# MBR.net
KiCad netlist of a schematic drawn in EAGLE
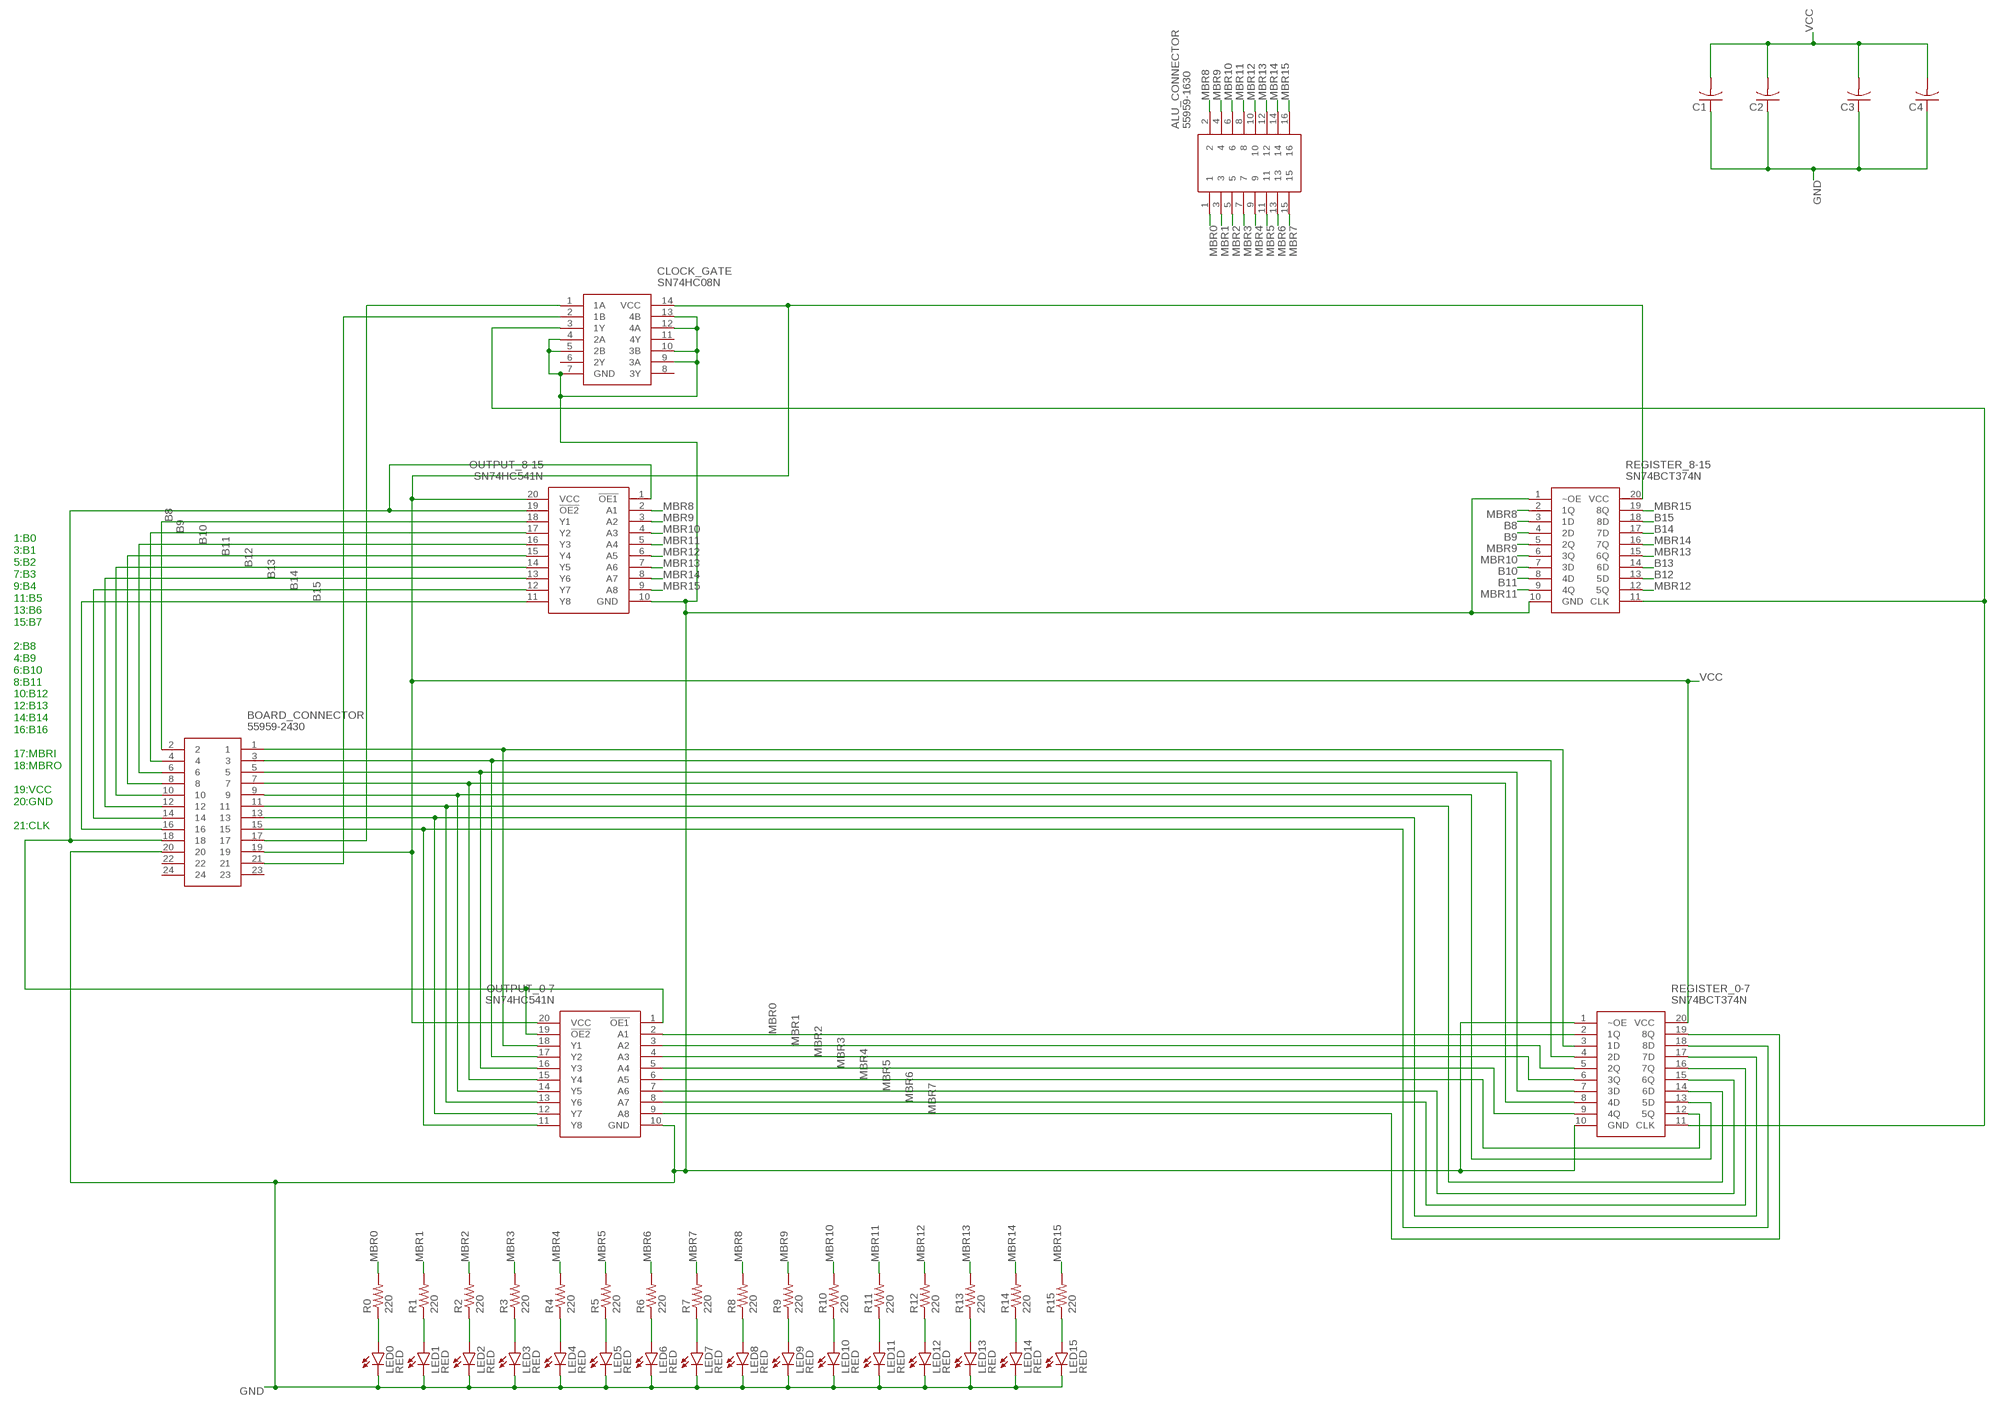
[diagram p0: schematic, sheet 1]

(export (version "E")
  (design (tool "Eeschema 10.0.6"))
  (components
    (comp (ref "ALU_CONNECTOR")
      (value "55959-1630")
      (footprint "eagle-import:SHDR16W65P250X200_2X8_1940X140")
      (fields (field (name "MOUSER_PART_NUMBER") "538-55959-1630"))
      (libsource (lib "eagle-import") (part "55959-1630"))
    )
    (comp (ref "BOARD_CONNECTOR")
      (value "55959-2430")
      (footprint "eagle-import:559592430")
      (fields (field (name "MOUSER_PART_NUMBER") "538-55959-2430"))
      (libsource (lib "eagle-import") (part "55959-2430"))
    )
    (comp (ref "C1")
      (value "C-US025-024X044")
      (footprint "eagle-import:C025-024X044")
      (libsource (lib "eagle-import") (part "C-US025-024X044"))
    )
    (comp (ref "C2")
      (value "C-US025-024X044")
      (footprint "eagle-import:C025-024X044")
      (libsource (lib "eagle-import") (part "C-US025-024X044"))
    )
    (comp (ref "C3")
      (value "C-US025-024X044")
      (footprint "eagle-import:C025-024X044")
      (libsource (lib "eagle-import") (part "C-US025-024X044"))
    )
    (comp (ref "C4")
      (value "C-US025-024X044")
      (footprint "eagle-import:C025-024X044")
      (libsource (lib "eagle-import") (part "C-US025-024X044"))
    )
    (comp (ref "CLOCK_GATE")
      (value "SN74HC08N")
      (footprint "eagle-import:DIP794W53P254L1930H508Q14N")
      (fields (field (name "MOUSER_PART_NUMBER") "595-SN74HC08N"))
      (libsource (lib "eagle-import") (part "SN74HC08N"))
    )
    (comp (ref "LED0")
      (value "RED")
      (footprint "eagle-import:LED3MM")
      (libsource (lib "eagle-import") (part "LED3MM"))
    )
    (comp (ref "LED1")
      (value "RED")
      (footprint "eagle-import:LED3MM")
      (libsource (lib "eagle-import") (part "LED3MM"))
    )
    (comp (ref "LED2")
      (value "RED")
      (footprint "eagle-import:LED3MM")
      (libsource (lib "eagle-import") (part "LED3MM"))
    )
    (comp (ref "LED3")
      (value "RED")
      (footprint "eagle-import:LED3MM")
      (libsource (lib "eagle-import") (part "LED3MM"))
    )
    (comp (ref "LED4")
      (value "RED")
      (footprint "eagle-import:LED3MM")
      (libsource (lib "eagle-import") (part "LED3MM"))
    )
    (comp (ref "LED5")
      (value "RED")
      (footprint "eagle-import:LED3MM")
      (libsource (lib "eagle-import") (part "LED3MM"))
    )
    (comp (ref "LED6")
      (value "RED")
      (footprint "eagle-import:LED3MM")
      (libsource (lib "eagle-import") (part "LED3MM"))
    )
    (comp (ref "LED7")
      (value "RED")
      (footprint "eagle-import:LED3MM")
      (libsource (lib "eagle-import") (part "LED3MM"))
    )
    (comp (ref "LED8")
      (value "RED")
      (footprint "eagle-import:LED3MM")
      (libsource (lib "eagle-import") (part "LED3MM"))
    )
    (comp (ref "LED9")
      (value "RED")
      (footprint "eagle-import:LED3MM")
      (libsource (lib "eagle-import") (part "LED3MM"))
    )
    (comp (ref "LED10")
      (value "RED")
      (footprint "eagle-import:LED3MM")
      (libsource (lib "eagle-import") (part "LED3MM"))
    )
    (comp (ref "LED11")
      (value "RED")
      (footprint "eagle-import:LED3MM")
      (libsource (lib "eagle-import") (part "LED3MM"))
    )
    (comp (ref "LED12")
      (value "RED")
      (footprint "eagle-import:LED3MM")
      (libsource (lib "eagle-import") (part "LED3MM"))
    )
    (comp (ref "LED13")
      (value "RED")
      (footprint "eagle-import:LED3MM")
      (libsource (lib "eagle-import") (part "LED3MM"))
    )
    (comp (ref "LED14")
      (value "RED")
      (footprint "eagle-import:LED3MM")
      (libsource (lib "eagle-import") (part "LED3MM"))
    )
    (comp (ref "LED15")
      (value "RED")
      (footprint "eagle-import:LED3MM")
      (libsource (lib "eagle-import") (part "LED3MM"))
    )
    (comp (ref "OUTPUT_0-7")
      (value "SN74HC541N")
      (footprint "eagle-import:DIP794W53P254L2540H508Q20N")
      (fields (field (name "MOUSER_PART_NUMBER") "595-SN74HC541N"))
      (libsource (lib "eagle-import") (part "SN74HC541N"))
    )
    (comp (ref "OUTPUT_8-15")
      (value "SN74HC541N")
      (footprint "eagle-import:DIP794W53P254L2540H508Q20N")
      (fields (field (name "MOUSER_PART_NUMBER") "595-SN74HC541N"))
      (libsource (lib "eagle-import") (part "SN74HC541N"))
    )
    (comp (ref "R0")
      (value "220")
      (footprint "eagle-import:0204_7")
      (libsource (lib "eagle-import") (part "R-US_0204/7"))
    )
    (comp (ref "R1")
      (value "220")
      (footprint "eagle-import:0204_7")
      (libsource (lib "eagle-import") (part "R-US_0204/7"))
    )
    (comp (ref "R2")
      (value "220")
      (footprint "eagle-import:0204_7")
      (libsource (lib "eagle-import") (part "R-US_0204/7"))
    )
    (comp (ref "R3")
      (value "220")
      (footprint "eagle-import:0204_7")
      (libsource (lib "eagle-import") (part "R-US_0204/7"))
    )
    (comp (ref "R4")
      (value "220")
      (footprint "eagle-import:0204_7")
      (libsource (lib "eagle-import") (part "R-US_0204/7"))
    )
    (comp (ref "R5")
      (value "220")
      (footprint "eagle-import:0204_7")
      (libsource (lib "eagle-import") (part "R-US_0204/7"))
    )
    (comp (ref "R6")
      (value "220")
      (footprint "eagle-import:0204_7")
      (libsource (lib "eagle-import") (part "R-US_0204/7"))
    )
    (comp (ref "R7")
      (value "220")
      (footprint "eagle-import:0204_7")
      (libsource (lib "eagle-import") (part "R-US_0204/7"))
    )
    (comp (ref "R8")
      (value "220")
      (footprint "eagle-import:0204_7")
      (libsource (lib "eagle-import") (part "R-US_0204/7"))
    )
    (comp (ref "R9")
      (value "220")
      (footprint "eagle-import:0204_7")
      (libsource (lib "eagle-import") (part "R-US_0204/7"))
    )
    (comp (ref "R10")
      (value "220")
      (footprint "eagle-import:0204_7")
      (libsource (lib "eagle-import") (part "R-US_0204/7"))
    )
    (comp (ref "R11")
      (value "220")
      (footprint "eagle-import:0204_7")
      (libsource (lib "eagle-import") (part "R-US_0204/7"))
    )
    (comp (ref "R12")
      (value "220")
      (footprint "eagle-import:0204_7")
      (libsource (lib "eagle-import") (part "R-US_0204/7"))
    )
    (comp (ref "R13")
      (value "220")
      (footprint "eagle-import:0204_7")
      (libsource (lib "eagle-import") (part "R-US_0204/7"))
    )
    (comp (ref "R14")
      (value "220")
      (footprint "eagle-import:0204_7")
      (libsource (lib "eagle-import") (part "R-US_0204/7"))
    )
    (comp (ref "R15")
      (value "220")
      (footprint "eagle-import:0204_7")
      (libsource (lib "eagle-import") (part "R-US_0204/7"))
    )
    (comp (ref "REGISTER_0-7")
      (value "SN74BCT374N")
      (footprint "eagle-import:DIP254P762X508-20")
      (fields (field (name "MOUSER_PART_NUMBER") "595-SN74BCT374N"))
      (libsource (lib "eagle-import") (part "SN74BCT374N"))
    )
    (comp (ref "REGISTER_8-15")
      (value "SN74BCT374N")
      (footprint "eagle-import:DIP254P762X508-20")
      (fields (field (name "MOUSER_PART_NUMBER") "595-SN74BCT374N"))
      (libsource (lib "eagle-import") (part "SN74BCT374N"))
    )
  )
  (nets
    (net (code "1") (name "/B8") (class "Default")
      (node (ref "BOARD_CONNECTOR") (pin "2") (pinfunction "2_2") (pintype "bidirectional"))
      (node (ref "OUTPUT_8-15") (pin "18") (pinfunction "Y1_18") (pintype "bidirectional"))
      (node (ref "REGISTER_8-15") (pin "3") (pinfunction "1D_3") (pintype "bidirectional"))
    )
    (net (code "2") (name "/B9") (class "Default")
      (node (ref "BOARD_CONNECTOR") (pin "4") (pinfunction "4_4") (pintype "bidirectional"))
      (node (ref "OUTPUT_8-15") (pin "17") (pinfunction "Y2_17") (pintype "bidirectional"))
      (node (ref "REGISTER_8-15") (pin "4") (pinfunction "2D_4") (pintype "bidirectional"))
    )
    (net (code "3") (name "/B10") (class "Default")
      (node (ref "BOARD_CONNECTOR") (pin "6") (pinfunction "6_6") (pintype "bidirectional"))
      (node (ref "OUTPUT_8-15") (pin "16") (pinfunction "Y3_16") (pintype "bidirectional"))
      (node (ref "REGISTER_8-15") (pin "7") (pinfunction "3D_7") (pintype "bidirectional"))
    )
    (net (code "4") (name "/B11") (class "Default")
      (node (ref "BOARD_CONNECTOR") (pin "8") (pinfunction "8_8") (pintype "bidirectional"))
      (node (ref "OUTPUT_8-15") (pin "15") (pinfunction "Y4_15") (pintype "bidirectional"))
      (node (ref "REGISTER_8-15") (pin "8") (pinfunction "4D_8") (pintype "bidirectional"))
    )
    (net (code "5") (name "/B12") (class "Default")
      (node (ref "BOARD_CONNECTOR") (pin "10") (pinfunction "10_10") (pintype "bidirectional"))
      (node (ref "OUTPUT_8-15") (pin "14") (pinfunction "Y5_14") (pintype "bidirectional"))
      (node (ref "REGISTER_8-15") (pin "13") (pinfunction "5D_13") (pintype "bidirectional"))
    )
    (net (code "6") (name "/B13") (class "Default")
      (node (ref "BOARD_CONNECTOR") (pin "12") (pinfunction "12_12") (pintype "bidirectional"))
      (node (ref "OUTPUT_8-15") (pin "13") (pinfunction "Y6_13") (pintype "bidirectional"))
      (node (ref "REGISTER_8-15") (pin "14") (pinfunction "6D_14") (pintype "bidirectional"))
    )
    (net (code "7") (name "/B14") (class "Default")
      (node (ref "BOARD_CONNECTOR") (pin "14") (pinfunction "14_14") (pintype "bidirectional"))
      (node (ref "OUTPUT_8-15") (pin "12") (pinfunction "Y7_12") (pintype "bidirectional"))
      (node (ref "REGISTER_8-15") (pin "17") (pinfunction "7D_17") (pintype "bidirectional"))
    )
    (net (code "8") (name "/B15") (class "Default")
      (node (ref "BOARD_CONNECTOR") (pin "16") (pinfunction "16_16") (pintype "bidirectional"))
      (node (ref "OUTPUT_8-15") (pin "11") (pinfunction "Y8_11") (pintype "bidirectional"))
      (node (ref "REGISTER_8-15") (pin "18") (pinfunction "8D_18") (pintype "bidirectional"))
    )
    (net (code "9") (name "/GND") (class "Default")
      (node (ref "BOARD_CONNECTOR") (pin "20") (pinfunction "20_20") (pintype "bidirectional"))
      (node (ref "C1") (pin "1") (pinfunction "1_1") (pintype "passive"))
      (node (ref "C2") (pin "1") (pinfunction "1_1") (pintype "passive"))
      (node (ref "C3") (pin "1") (pinfunction "1_1") (pintype "passive"))
      (node (ref "C4") (pin "1") (pinfunction "1_1") (pintype "passive"))
      (node (ref "CLOCK_GATE") (pin "10") (pinfunction "3B_10") (pintype "bidirectional"))
      (node (ref "CLOCK_GATE") (pin "12") (pinfunction "4A_12") (pintype "bidirectional"))
      (node (ref "CLOCK_GATE") (pin "13") (pinfunction "4B_13") (pintype "bidirectional"))
      (node (ref "CLOCK_GATE") (pin "4") (pinfunction "2A_4") (pintype "bidirectional"))
      (node (ref "CLOCK_GATE") (pin "5") (pinfunction "2B_5") (pintype "bidirectional"))
      (node (ref "CLOCK_GATE") (pin "7") (pinfunction "GND_7") (pintype "bidirectional"))
      (node (ref "CLOCK_GATE") (pin "9") (pinfunction "3A_9") (pintype "bidirectional"))
      (node (ref "LED0") (pin "K") (pinfunction "C_K") (pintype "passive"))
      (node (ref "LED1") (pin "K") (pinfunction "C_K") (pintype "passive"))
      (node (ref "LED10") (pin "K") (pinfunction "C_K") (pintype "passive"))
      (node (ref "LED11") (pin "K") (pinfunction "C_K") (pintype "passive"))
      (node (ref "LED12") (pin "K") (pinfunction "C_K") (pintype "passive"))
      (node (ref "LED13") (pin "K") (pinfunction "C_K") (pintype "passive"))
      (node (ref "LED14") (pin "K") (pinfunction "C_K") (pintype "passive"))
      (node (ref "LED15") (pin "K") (pinfunction "C_K") (pintype "passive"))
      (node (ref "LED2") (pin "K") (pinfunction "C_K") (pintype "passive"))
      (node (ref "LED3") (pin "K") (pinfunction "C_K") (pintype "passive"))
      (node (ref "LED4") (pin "K") (pinfunction "C_K") (pintype "passive"))
      (node (ref "LED5") (pin "K") (pinfunction "C_K") (pintype "passive"))
      (node (ref "LED6") (pin "K") (pinfunction "C_K") (pintype "passive"))
      (node (ref "LED7") (pin "K") (pinfunction "C_K") (pintype "passive"))
      (node (ref "LED8") (pin "K") (pinfunction "C_K") (pintype "passive"))
      (node (ref "LED9") (pin "K") (pinfunction "C_K") (pintype "passive"))
      (node (ref "OUTPUT_0-7") (pin "10") (pinfunction "GND_10") (pintype "bidirectional"))
      (node (ref "OUTPUT_8-15") (pin "10") (pinfunction "GND_10") (pintype "bidirectional"))
      (node (ref "REGISTER_0-7") (pin "1") (pinfunction "~{OE}_1") (pintype "bidirectional"))
      (node (ref "REGISTER_0-7") (pin "10") (pinfunction "GND_10") (pintype "bidirectional"))
      (node (ref "REGISTER_8-15") (pin "1") (pinfunction "~{OE}_1") (pintype "bidirectional"))
      (node (ref "REGISTER_8-15") (pin "10") (pinfunction "GND_10") (pintype "bidirectional"))
    )
    (net (code "10") (name "/MBR0") (class "Default")
      (node (ref "ALU_CONNECTOR") (pin "1") (pinfunction "1_1") (pintype "bidirectional"))
      (node (ref "OUTPUT_0-7") (pin "2") (pinfunction "A1_2") (pintype "bidirectional"))
      (node (ref "R0") (pin "2") (pinfunction "2_2") (pintype "passive"))
      (node (ref "REGISTER_0-7") (pin "2") (pinfunction "1Q_2") (pintype "bidirectional"))
    )
    (net (code "11") (name "/MBR1") (class "Default")
      (node (ref "ALU_CONNECTOR") (pin "3") (pinfunction "3_3") (pintype "bidirectional"))
      (node (ref "OUTPUT_0-7") (pin "3") (pinfunction "A2_3") (pintype "bidirectional"))
      (node (ref "R1") (pin "2") (pinfunction "2_2") (pintype "passive"))
      (node (ref "REGISTER_0-7") (pin "5") (pinfunction "2Q_5") (pintype "bidirectional"))
    )
    (net (code "12") (name "/MBR2") (class "Default")
      (node (ref "ALU_CONNECTOR") (pin "5") (pinfunction "5_5") (pintype "bidirectional"))
      (node (ref "OUTPUT_0-7") (pin "4") (pinfunction "A3_4") (pintype "bidirectional"))
      (node (ref "R2") (pin "2") (pinfunction "2_2") (pintype "passive"))
      (node (ref "REGISTER_0-7") (pin "6") (pinfunction "3Q_6") (pintype "bidirectional"))
    )
    (net (code "13") (name "/MBR3") (class "Default")
      (node (ref "ALU_CONNECTOR") (pin "7") (pinfunction "7_7") (pintype "bidirectional"))
      (node (ref "OUTPUT_0-7") (pin "5") (pinfunction "A4_5") (pintype "bidirectional"))
      (node (ref "R3") (pin "2") (pinfunction "2_2") (pintype "passive"))
      (node (ref "REGISTER_0-7") (pin "9") (pinfunction "4Q_9") (pintype "bidirectional"))
    )
    (net (code "14") (name "/MBR4") (class "Default")
      (node (ref "ALU_CONNECTOR") (pin "9") (pinfunction "9_9") (pintype "bidirectional"))
      (node (ref "OUTPUT_0-7") (pin "6") (pinfunction "A5_6") (pintype "bidirectional"))
      (node (ref "R4") (pin "2") (pinfunction "2_2") (pintype "passive"))
      (node (ref "REGISTER_0-7") (pin "12") (pinfunction "5Q_12") (pintype "bidirectional"))
    )
    (net (code "15") (name "/MBR5") (class "Default")
      (node (ref "ALU_CONNECTOR") (pin "11") (pinfunction "11_11") (pintype "bidirectional"))
      (node (ref "OUTPUT_0-7") (pin "7") (pinfunction "A6_7") (pintype "bidirectional"))
      (node (ref "R5") (pin "2") (pinfunction "2_2") (pintype "passive"))
      (node (ref "REGISTER_0-7") (pin "15") (pinfunction "6Q_15") (pintype "bidirectional"))
    )
    (net (code "16") (name "/MBR6") (class "Default")
      (node (ref "ALU_CONNECTOR") (pin "13") (pinfunction "13_13") (pintype "bidirectional"))
      (node (ref "OUTPUT_0-7") (pin "8") (pinfunction "A7_8") (pintype "bidirectional"))
      (node (ref "R6") (pin "2") (pinfunction "2_2") (pintype "passive"))
      (node (ref "REGISTER_0-7") (pin "16") (pinfunction "7Q_16") (pintype "bidirectional"))
    )
    (net (code "17") (name "/MBR7") (class "Default")
      (node (ref "ALU_CONNECTOR") (pin "15") (pinfunction "15_15") (pintype "bidirectional"))
      (node (ref "OUTPUT_0-7") (pin "9") (pinfunction "A8_9") (pintype "bidirectional"))
      (node (ref "R7") (pin "2") (pinfunction "2_2") (pintype "passive"))
      (node (ref "REGISTER_0-7") (pin "19") (pinfunction "8Q_19") (pintype "bidirectional"))
    )
    (net (code "18") (name "/MBR8") (class "Default")
      (node (ref "ALU_CONNECTOR") (pin "2") (pinfunction "2_2") (pintype "bidirectional"))
      (node (ref "OUTPUT_8-15") (pin "2") (pinfunction "A1_2") (pintype "bidirectional"))
      (node (ref "R8") (pin "2") (pinfunction "2_2") (pintype "passive"))
      (node (ref "REGISTER_8-15") (pin "2") (pinfunction "1Q_2") (pintype "bidirectional"))
    )
    (net (code "19") (name "/MBR9") (class "Default")
      (node (ref "ALU_CONNECTOR") (pin "4") (pinfunction "4_4") (pintype "bidirectional"))
      (node (ref "OUTPUT_8-15") (pin "3") (pinfunction "A2_3") (pintype "bidirectional"))
      (node (ref "R9") (pin "2") (pinfunction "2_2") (pintype "passive"))
      (node (ref "REGISTER_8-15") (pin "5") (pinfunction "2Q_5") (pintype "bidirectional"))
    )
    (net (code "20") (name "/MBR10") (class "Default")
      (node (ref "ALU_CONNECTOR") (pin "6") (pinfunction "6_6") (pintype "bidirectional"))
      (node (ref "OUTPUT_8-15") (pin "4") (pinfunction "A3_4") (pintype "bidirectional"))
      (node (ref "R10") (pin "2") (pinfunction "2_2") (pintype "passive"))
      (node (ref "REGISTER_8-15") (pin "6") (pinfunction "3Q_6") (pintype "bidirectional"))
    )
    (net (code "21") (name "/MBR11") (class "Default")
      (node (ref "ALU_CONNECTOR") (pin "8") (pinfunction "8_8") (pintype "bidirectional"))
      (node (ref "OUTPUT_8-15") (pin "5") (pinfunction "A4_5") (pintype "bidirectional"))
      (node (ref "R11") (pin "2") (pinfunction "2_2") (pintype "passive"))
      (node (ref "REGISTER_8-15") (pin "9") (pinfunction "4Q_9") (pintype "bidirectional"))
    )
    (net (code "22") (name "/MBR12") (class "Default")
      (node (ref "ALU_CONNECTOR") (pin "10") (pinfunction "10_10") (pintype "bidirectional"))
      (node (ref "OUTPUT_8-15") (pin "6") (pinfunction "A5_6") (pintype "bidirectional"))
      (node (ref "R12") (pin "2") (pinfunction "2_2") (pintype "passive"))
      (node (ref "REGISTER_8-15") (pin "12") (pinfunction "5Q_12") (pintype "bidirectional"))
    )
    (net (code "23") (name "/MBR13") (class "Default")
      (node (ref "ALU_CONNECTOR") (pin "12") (pinfunction "12_12") (pintype "bidirectional"))
      (node (ref "OUTPUT_8-15") (pin "7") (pinfunction "A6_7") (pintype "bidirectional"))
      (node (ref "R13") (pin "2") (pinfunction "2_2") (pintype "passive"))
      (node (ref "REGISTER_8-15") (pin "15") (pinfunction "6Q_15") (pintype "bidirectional"))
    )
    (net (code "24") (name "/MBR14") (class "Default")
      (node (ref "ALU_CONNECTOR") (pin "14") (pinfunction "14_14") (pintype "bidirectional"))
      (node (ref "OUTPUT_8-15") (pin "8") (pinfunction "A7_8") (pintype "bidirectional"))
      (node (ref "R14") (pin "2") (pinfunction "2_2") (pintype "passive"))
      (node (ref "REGISTER_8-15") (pin "16") (pinfunction "7Q_16") (pintype "bidirectional"))
    )
    (net (code "25") (name "/MBR15") (class "Default")
      (node (ref "ALU_CONNECTOR") (pin "16") (pinfunction "16_16") (pintype "bidirectional"))
      (node (ref "OUTPUT_8-15") (pin "9") (pinfunction "A8_9") (pintype "bidirectional"))
      (node (ref "R15") (pin "2") (pinfunction "2_2") (pintype "passive"))
      (node (ref "REGISTER_8-15") (pin "19") (pinfunction "8Q_19") (pintype "bidirectional"))
    )
    (net (code "26") (name "/VCC") (class "Default")
      (node (ref "BOARD_CONNECTOR") (pin "19") (pinfunction "19_19") (pintype "bidirectional"))
      (node (ref "C1") (pin "2") (pinfunction "2_2") (pintype "passive"))
      (node (ref "C2") (pin "2") (pinfunction "2_2") (pintype "passive"))
      (node (ref "C3") (pin "2") (pinfunction "2_2") (pintype "passive"))
      (node (ref "C4") (pin "2") (pinfunction "2_2") (pintype "passive"))
      (node (ref "CLOCK_GATE") (pin "14") (pinfunction "VCC_14") (pintype "bidirectional"))
      (node (ref "OUTPUT_0-7") (pin "20") (pinfunction "VCC_20") (pintype "bidirectional"))
      (node (ref "OUTPUT_8-15") (pin "20") (pinfunction "VCC_20") (pintype "bidirectional"))
      (node (ref "REGISTER_0-7") (pin "20") (pinfunction "VCC_20") (pintype "bidirectional"))
      (node (ref "REGISTER_8-15") (pin "20") (pinfunction "VCC_20") (pintype "bidirectional"))
    )
    (net (code "27") (name "Net-(CLOCK_GATE-1A)") (class "Default")
      (node (ref "BOARD_CONNECTOR") (pin "17") (pinfunction "17_17") (pintype "bidirectional"))
      (node (ref "CLOCK_GATE") (pin "1") (pinfunction "1A_1") (pintype "bidirectional"))
    )
    (net (code "28") (name "Net-(CLOCK_GATE-1B)") (class "Default")
      (node (ref "BOARD_CONNECTOR") (pin "21") (pinfunction "21_21") (pintype "bidirectional"))
      (node (ref "CLOCK_GATE") (pin "2") (pinfunction "1B_2") (pintype "bidirectional"))
    )
    (net (code "29") (name "Net-(CLOCK_GATE-1Y)") (class "Default")
      (node (ref "CLOCK_GATE") (pin "3") (pinfunction "1Y_3") (pintype "bidirectional"))
      (node (ref "REGISTER_0-7") (pin "11") (pinfunction "CLK_11") (pintype "bidirectional"))
      (node (ref "REGISTER_8-15") (pin "11") (pinfunction "CLK_11") (pintype "bidirectional"))
    )
    (net (code "30") (name "Net-(LED0-PadA)") (class "Default")
      (node (ref "LED0") (pin "A") (pinfunction "A_A") (pintype "passive"))
      (node (ref "R0") (pin "1") (pinfunction "1_1") (pintype "passive"))
    )
    (net (code "31") (name "Net-(LED1-PadA)") (class "Default")
      (node (ref "LED1") (pin "A") (pinfunction "A_A") (pintype "passive"))
      (node (ref "R1") (pin "1") (pinfunction "1_1") (pintype "passive"))
    )
    (net (code "32") (name "Net-(LED2-PadA)") (class "Default")
      (node (ref "LED2") (pin "A") (pinfunction "A_A") (pintype "passive"))
      (node (ref "R2") (pin "1") (pinfunction "1_1") (pintype "passive"))
    )
    (net (code "33") (name "Net-(LED3-PadA)") (class "Default")
      (node (ref "LED3") (pin "A") (pinfunction "A_A") (pintype "passive"))
      (node (ref "R3") (pin "1") (pinfunction "1_1") (pintype "passive"))
    )
    (net (code "34") (name "Net-(LED4-PadA)") (class "Default")
      (node (ref "LED4") (pin "A") (pinfunction "A_A") (pintype "passive"))
      (node (ref "R4") (pin "1") (pinfunction "1_1") (pintype "passive"))
    )
    (net (code "35") (name "Net-(LED5-PadA)") (class "Default")
      (node (ref "LED5") (pin "A") (pinfunction "A_A") (pintype "passive"))
      (node (ref "R5") (pin "1") (pinfunction "1_1") (pintype "passive"))
    )
    (net (code "36") (name "Net-(LED6-PadA)") (class "Default")
      (node (ref "LED6") (pin "A") (pinfunction "A_A") (pintype "passive"))
      (node (ref "R6") (pin "1") (pinfunction "1_1") (pintype "passive"))
    )
    (net (code "37") (name "Net-(LED7-PadA)") (class "Default")
      (node (ref "LED7") (pin "A") (pinfunction "A_A") (pintype "passive"))
      (node (ref "R7") (pin "1") (pinfunction "1_1") (pintype "passive"))
    )
    (net (code "38") (name "Net-(LED8-PadA)") (class "Default")
      (node (ref "LED8") (pin "A") (pinfunction "A_A") (pintype "passive"))
      (node (ref "R8") (pin "1") (pinfunction "1_1") (pintype "passive"))
    )
    (net (code "39") (name "Net-(LED9-PadA)") (class "Default")
      (node (ref "LED9") (pin "A") (pinfunction "A_A") (pintype "passive"))
      (node (ref "R9") (pin "1") (pinfunction "1_1") (pintype "passive"))
    )
    (net (code "40") (name "Net-(LED10-PadA)") (class "Default")
      (node (ref "LED10") (pin "A") (pinfunction "A_A") (pintype "passive"))
      (node (ref "R10") (pin "1") (pinfunction "1_1") (pintype "passive"))
    )
    (net (code "41") (name "Net-(LED11-PadA)") (class "Default")
      (node (ref "LED11") (pin "A") (pinfunction "A_A") (pintype "passive"))
      (node (ref "R11") (pin "1") (pinfunction "1_1") (pintype "passive"))
    )
    (net (code "42") (name "Net-(LED12-PadA)") (class "Default")
      (node (ref "LED12") (pin "A") (pinfunction "A_A") (pintype "passive"))
      (node (ref "R12") (pin "1") (pinfunction "1_1") (pintype "passive"))
    )
    (net (code "43") (name "Net-(LED13-PadA)") (class "Default")
      (node (ref "LED13") (pin "A") (pinfunction "A_A") (pintype "passive"))
      (node (ref "R13") (pin "1") (pinfunction "1_1") (pintype "passive"))
    )
    (net (code "44") (name "Net-(LED14-PadA)") (class "Default")
      (node (ref "LED14") (pin "A") (pinfunction "A_A") (pintype "passive"))
      (node (ref "R14") (pin "1") (pinfunction "1_1") (pintype "passive"))
    )
    (net (code "45") (name "Net-(LED15-PadA)") (class "Default")
      (node (ref "LED15") (pin "A") (pinfunction "A_A") (pintype "passive"))
      (node (ref "R15") (pin "1") (pinfunction "1_1") (pintype "passive"))
    )
    (net (code "46") (name "Net-(OUTPUT_0-7-Y1)") (class "Default")
      (node (ref "BOARD_CONNECTOR") (pin "1") (pinfunction "1_1") (pintype "bidirectional"))
      (node (ref "OUTPUT_0-7") (pin "18") (pinfunction "Y1_18") (pintype "bidirectional"))
      (node (ref "REGISTER_0-7") (pin "3") (pinfunction "1D_3") (pintype "bidirectional"))
    )
    (net (code "47") (name "Net-(OUTPUT_0-7-Y2)") (class "Default")
      (node (ref "BOARD_CONNECTOR") (pin "3") (pinfunction "3_3") (pintype "bidirectional"))
      (node (ref "OUTPUT_0-7") (pin "17") (pinfunction "Y2_17") (pintype "bidirectional"))
      (node (ref "REGISTER_0-7") (pin "4") (pinfunction "2D_4") (pintype "bidirectional"))
    )
    (net (code "48") (name "Net-(OUTPUT_0-7-Y3)") (class "Default")
      (node (ref "BOARD_CONNECTOR") (pin "5") (pinfunction "5_5") (pintype "bidirectional"))
      (node (ref "OUTPUT_0-7") (pin "16") (pinfunction "Y3_16") (pintype "bidirectional"))
      (node (ref "REGISTER_0-7") (pin "7") (pinfunction "3D_7") (pintype "bidirectional"))
    )
    (net (code "49") (name "Net-(OUTPUT_0-7-Y4)") (class "Default")
      (node (ref "BOARD_CONNECTOR") (pin "7") (pinfunction "7_7") (pintype "bidirectional"))
      (node (ref "OUTPUT_0-7") (pin "15") (pinfunction "Y4_15") (pintype "bidirectional"))
      (node (ref "REGISTER_0-7") (pin "8") (pinfunction "4D_8") (pintype "bidirectional"))
    )
    (net (code "50") (name "Net-(OUTPUT_0-7-Y5)") (class "Default")
      (node (ref "BOARD_CONNECTOR") (pin "9") (pinfunction "9_9") (pintype "bidirectional"))
      (node (ref "OUTPUT_0-7") (pin "14") (pinfunction "Y5_14") (pintype "bidirectional"))
      (node (ref "REGISTER_0-7") (pin "13") (pinfunction "5D_13") (pintype "bidirectional"))
    )
    (net (code "51") (name "Net-(OUTPUT_0-7-Y6)") (class "Default")
      (node (ref "BOARD_CONNECTOR") (pin "11") (pinfunction "11_11") (pintype "bidirectional"))
      (node (ref "OUTPUT_0-7") (pin "13") (pinfunction "Y6_13") (pintype "bidirectional"))
      (node (ref "REGISTER_0-7") (pin "14") (pinfunction "6D_14") (pintype "bidirectional"))
    )
    (net (code "52") (name "Net-(OUTPUT_0-7-Y7)") (class "Default")
      (node (ref "BOARD_CONNECTOR") (pin "13") (pinfunction "13_13") (pintype "bidirectional"))
      (node (ref "OUTPUT_0-7") (pin "12") (pinfunction "Y7_12") (pintype "bidirectional"))
      (node (ref "REGISTER_0-7") (pin "17") (pinfunction "7D_17") (pintype "bidirectional"))
    )
    (net (code "53") (name "Net-(OUTPUT_0-7-Y8)") (class "Default")
      (node (ref "BOARD_CONNECTOR") (pin "15") (pinfunction "15_15") (pintype "bidirectional"))
      (node (ref "OUTPUT_0-7") (pin "11") (pinfunction "Y8_11") (pintype "bidirectional"))
      (node (ref "REGISTER_0-7") (pin "18") (pinfunction "8D_18") (pintype "bidirectional"))
    )
    (net (code "54") (name "Net-(OUTPUT_0-7-~{OE1})") (class "Default")
      (node (ref "BOARD_CONNECTOR") (pin "18") (pinfunction "18_18") (pintype "bidirectional"))
      (node (ref "OUTPUT_0-7") (pin "1") (pinfunction "~{OE1}_1") (pintype "bidirectional"))
      (node (ref "OUTPUT_0-7") (pin "19") (pinfunction "~{OE2}_19") (pintype "bidirectional"))
      (node (ref "OUTPUT_8-15") (pin "1") (pinfunction "~{OE1}_1") (pintype "bidirectional"))
      (node (ref "OUTPUT_8-15") (pin "19") (pinfunction "~{OE2}_19") (pintype "bidirectional"))
    )
    (net (code "55") (name "unconnected-(BOARD_CONNECTOR-Pad22)") (class "Default")
      (node (ref "BOARD_CONNECTOR") (pin "22") (pinfunction "22_22") (pintype "bidirectional"))
    )
    (net (code "56") (name "unconnected-(BOARD_CONNECTOR-Pad23)") (class "Default")
      (node (ref "BOARD_CONNECTOR") (pin "23") (pinfunction "23_23") (pintype "bidirectional"))
    )
    (net (code "57") (name "unconnected-(BOARD_CONNECTOR-Pad24)") (class "Default")
      (node (ref "BOARD_CONNECTOR") (pin "24") (pinfunction "24_24") (pintype "bidirectional"))
    )
    (net (code "58") (name "unconnected-(CLOCK_GATE-2Y-Pad6)") (class "Default")
      (node (ref "CLOCK_GATE") (pin "6") (pinfunction "2Y_6") (pintype "bidirectional"))
    )
    (net (code "59") (name "unconnected-(CLOCK_GATE-3Y-Pad8)") (class "Default")
      (node (ref "CLOCK_GATE") (pin "8") (pinfunction "3Y_8") (pintype "bidirectional"))
    )
    (net (code "60") (name "unconnected-(CLOCK_GATE-4Y-Pad11)") (class "Default")
      (node (ref "CLOCK_GATE") (pin "11") (pinfunction "4Y_11") (pintype "bidirectional"))
    )
  )
)
